# MainPower_Regulation.net
KiCad netlist of a schematic drawn in Altium Designer
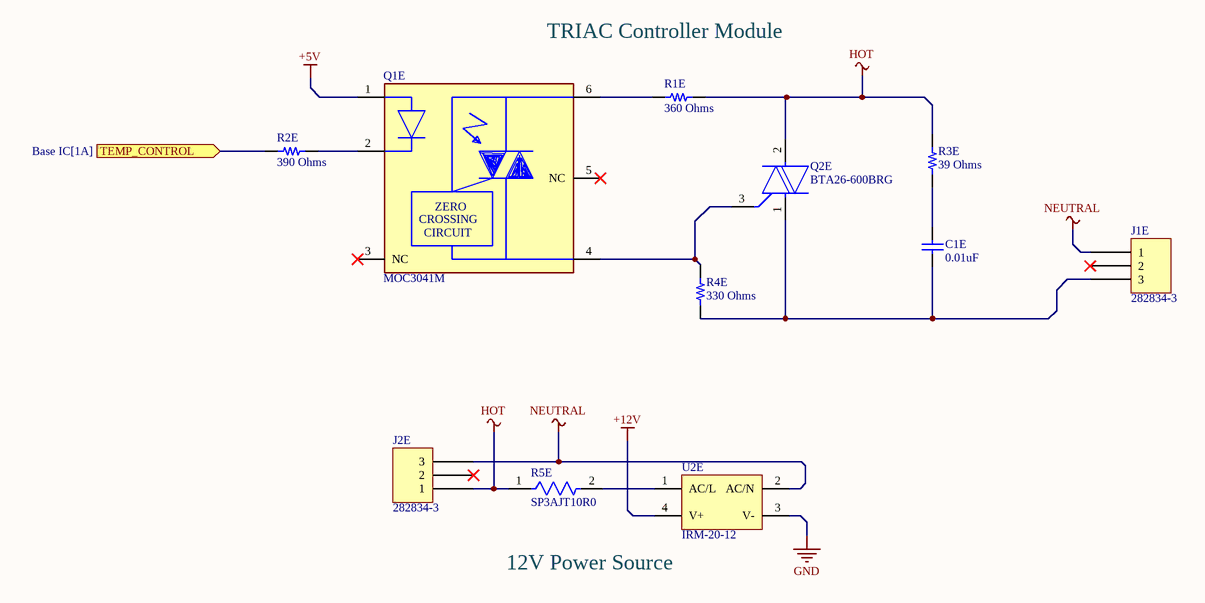
[diagram p0: MainPower & Regulation.SchDoc]

(export (version "E")
  (design (tool "Eeschema 10.0.6"))
  (components
    (comp (ref "C1E")
      (value "0.01uF")
      (footprint "WCAP-FTXX_L13W5H11_CS")
      (description "890334023006CS WCAP-FTXX Film Capacitor 10nF 310Vac")
      (fields (field (name "TOLERANCE") "10%"))
      (libsource (lib "Altium Content Vault") (part "Capacitor_Non-Polarized"))
    )
    (comp (ref "J1E")
      (value "282834-3")
      (footprint "TE 282834-3")
      (description "TERM BLK 3P SIDE ENT 2.54MM PCB")
      (fields (field (name "VOLTAGE") "150V") (field (name "MANUFACTURER") "TE Connectivity AMP Connectors"))
      (libsource (lib "") (part "3 Pin_1"))
    )
    (comp (ref "J2E")
      (value "282834-3")
      (footprint "TE 282834-3")
      (description "TERM BLK 3P SIDE ENT 2.54MM PCB")
      (fields (field (name "VOLTAGE") "150V") (field (name "MANUFACTURER") "TE Connectivity AMP Connectors"))
      (libsource (lib "Postgres Altium Library - altium_library") (part "3 Pin"))
    )
    (comp (ref "Q1E")
      (value "MOC3041M")
      (footprint "FP-646BX-MFG")
      (description "OPTOISOLATOR 4.17KV TRIAC 6DIP")
      (fields
        (field (name "OCTOPART") "https://octopart.com/moc3041m-on+semiconductor-84330395")
        (field (name "MANUFACTURER") "ON Semiconductor")
      )
      (libsource (lib "Altium Content Vault") (part "55d433852054a47a4af1c6890e72339"))
    )
    (comp (ref "Q2E")
      (value "BTA26-600BRG")
      (footprint "BTA26-600BRG")
      (libsource (lib "TRIAC") (part "BTA26-600BRG"))
    )
    (comp (ref "R1E")
      (value "360 Ohms")
      (footprint "RES 2512_6432")
      (description "RES 360 OHM 5% 1W 2512")
      (fields (field (name "PART NUMBER") "RK73B3ATTE361J") (field (name "TOLERANCE") "±5%"))
      (libsource (lib "Postgres Altium Library - altium_library") (part "Resistor"))
    )
    (comp (ref "R2E")
      (value "390 Ohms")
      (footprint "RES 0402_1005")
      (description "RES SMD 390 OHM 1% 1/16W 0402")
      (fields (field (name "PART NUMBER") "CR0402-FX-3900GLF") (field (name "TOLERANCE") "±1%"))
      (libsource (lib "Postgres Altium Library - altium_library") (part "Resistor"))
    )
    (comp (ref "R3E")
      (value "39 Ohms")
      (footprint "RES 2512_6432")
      (description "RES 39 OHM 5% 1W 2512")
      (fields (field (name "PART NUMBER") "RK73B3ATTE390J") (field (name "TOLERANCE") "±5%"))
      (libsource (lib "Postgres Altium Library - altium_library") (part "Resistor"))
    )
    (comp (ref "R4E")
      (value "330 Ohms")
      (footprint "RES 2512_6432")
      (description "RES 330 OHM 1% 1W 2512")
      (fields (field (name "PART NUMBER") "RK73H3ATTE3300F") (field (name "TOLERANCE") "±1%"))
      (libsource (lib "Postgres Altium Library - altium_library") (part "Resistor"))
    )
    (comp (ref "R5E")
      (value "SP3AJT10R0")
      (footprint "FP-SP3A-MFG")
      (description "RES 10 OHM 5% 4W AXIAL")
      (fields (field (name "TOLERANCE") "5%"))
      (libsource (lib "Altium Content Vault") (part "1029c3af85768c4190bb7ad29bc67b5"))
    )
    (comp (ref "U2E")
      (value "IRM-20-12")
      (footprint "MEANW-IRM-20-12")
      (description "Single Output Encapsulated Type, 12 V, 1.8 A, 21.6 W, -40 to 85 degC, 4-Pin THD, RoHS")
      (fields (field (name "MANUFACTURER") "Mean Well"))
      (libsource (lib "Altium Content Vault") (part "MEANW-IRM-20-12-4"))
    )
  )
  (nets
    (net (code "1") (name "+5V") (class "Default")
      (node (ref "Q1E") (pin "1") (pinfunction "A_1") (pintype "passive"))
    )
    (net (code "2") (name "+12V") (class "Default")
      (node (ref "U2E") (pin "4") (pinfunction "V+_4") (pintype "power_in"))
    )
    (net (code "3") (name "/TEMP_CONTROL") (class "Default")
      (node (ref "R2E") (pin "1") (pinfunction "1_1") (pintype "passive"))
    )
    (net (code "4") (name "GND") (class "Default")
      (node (ref "U2E") (pin "3") (pinfunction "V-_3") (pintype "power_in"))
    )
    (net (code "5") (name "HOT") (class "Default")
      (node (ref "J2E") (pin "1") (pinfunction "1_1") (pintype "passive"))
      (node (ref "Q2E") (pin "2") (pinfunction "A2_2") (pintype "passive"))
      (node (ref "R1E") (pin "2") (pinfunction "2_2") (pintype "passive"))
      (node (ref "R3E") (pin "2") (pinfunction "2_2") (pintype "passive"))
      (node (ref "R5E") (pin "1") (pinfunction "1_1") (pintype "passive"))
    )
    (net (code "6") (name "NEUTRAL") (class "Default")
      (node (ref "J1E") (pin "1") (pinfunction "1_1") (pintype "passive"))
      (node (ref "J2E") (pin "3") (pinfunction "3_3") (pintype "passive"))
      (node (ref "U2E") (pin "2") (pinfunction "AC/N_2") (pintype "passive"))
    )
    (net (code "7") (name "Net-(C1E-Pad2)") (class "Default")
      (node (ref "C1E") (pin "2") (pinfunction "2_2") (pintype "passive"))
      (node (ref "R3E") (pin "1") (pinfunction "1_1") (pintype "passive"))
    )
    (net (code "8") (name "Net-(Q1E-1_MAIN_TERM.)") (class "Default")
      (node (ref "Q1E") (pin "4") (pinfunction "1_MAIN_TERM._4") (pintype "passive"))
      (node (ref "Q2E") (pin "3") (pinfunction "G_3") (pintype "passive"))
      (node (ref "R4E") (pin "2") (pinfunction "2_2") (pintype "passive"))
    )
    (net (code "9") (name "Net-(Q1E-2_MAIN_TERM.)") (class "Default")
      (node (ref "Q1E") (pin "6") (pinfunction "2_MAIN_TERM._6") (pintype "passive"))
      (node (ref "R1E") (pin "1") (pinfunction "1_1") (pintype "passive"))
    )
    (net (code "10") (name "Net-(Q1E-C)") (class "Default")
      (node (ref "Q1E") (pin "2") (pinfunction "C_2") (pintype "passive"))
      (node (ref "R2E") (pin "2") (pinfunction "2_2") (pintype "passive"))
    )
    (net (code "11") (name "Net-(Q2E-A1)") (class "Default")
      (node (ref "C1E") (pin "1") (pinfunction "1_1") (pintype "passive"))
      (node (ref "J1E") (pin "3") (pinfunction "3_3") (pintype "passive"))
      (node (ref "Q2E") (pin "1") (pinfunction "A1_1") (pintype "passive"))
      (node (ref "R4E") (pin "1") (pinfunction "1_1") (pintype "passive"))
    )
    (net (code "12") (name "Net-(U2E-AC{slash}L)") (class "Default")
      (node (ref "R5E") (pin "2") (pinfunction "2_2") (pintype "passive"))
      (node (ref "U2E") (pin "1") (pinfunction "AC/L_1") (pintype "passive"))
    )
    (net (code "13") (name "unconnected-(J1E-Pad2)") (class "Default")
      (node (ref "J1E") (pin "2") (pinfunction "2_2") (pintype "passive+no_connect"))
    )
    (net (code "14") (name "unconnected-(J2E-Pad2)") (class "Default")
      (node (ref "J2E") (pin "2") (pinfunction "2_2") (pintype "passive+no_connect"))
    )
    (net (code "15") (name "unconnected-(Q1E-NC-Pad3)") (class "Default")
      (node (ref "Q1E") (pin "3") (pinfunction "NC_3") (pintype "passive+no_connect"))
    )
    (net (code "16") (name "unconnected-(Q1E-NC-Pad5)") (class "Default")
      (node (ref "Q1E") (pin "5") (pinfunction "NC_5") (pintype "passive+no_connect"))
    )
  )
)
